# 2_-_PWR.net
KiCad netlist of a schematic drawn in Altium Designer
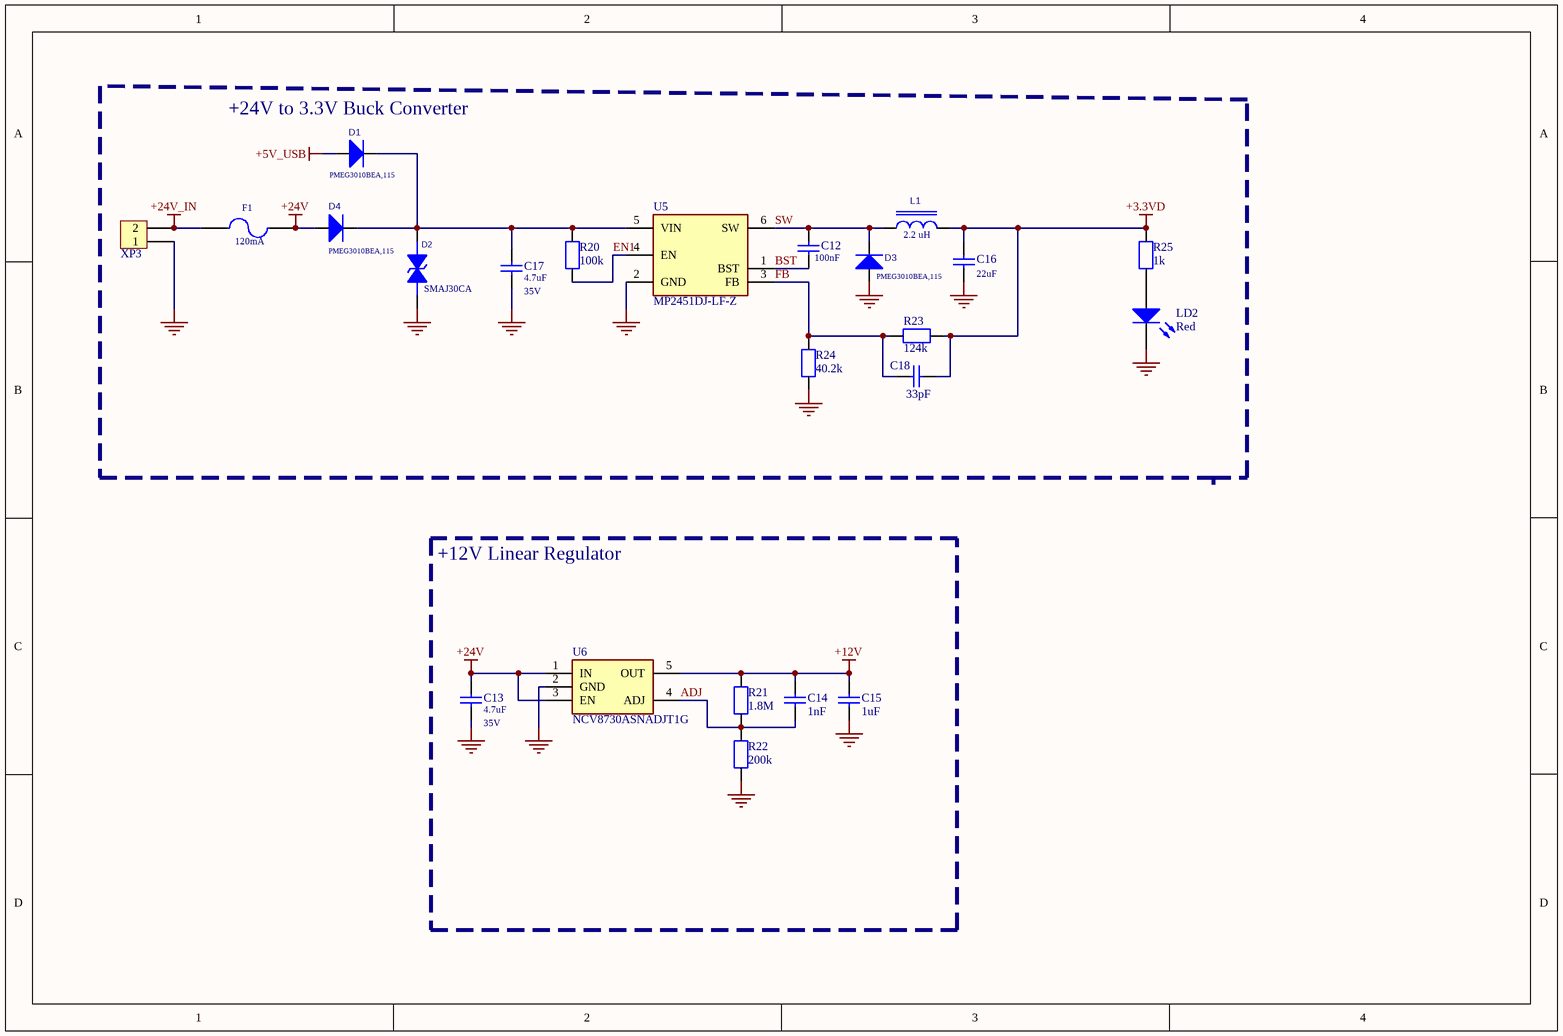
[diagram p0: [2] - PWR.SchDoc]

(export (version "E")
  (design (tool "Eeschema 10.0.6"))
  (components
    (comp (ref "C12")
      (value "100nF")
      (footprint "CC0603")
      (description "SMD Multilayer Ceramic Capacitor, 0.1 µF, 50 V, 0603 [1608 Metric], ± 10%, X7R, MC")
      (fields
        (field (name "MANUFACTURER") "MULTICOMP")
        (field (name "MANUFACTURER PART NUMBER") "MC0603B104K500CT")
      )
      (libsource (lib "YAQF") (part "Capacitors_SMD"))
    )
    (comp (ref "C13")
      (value "4.7uF")
      (footprint "CC0805")
      (description "SMD Multilayer Ceramic Capacitor, 4.7 µF, 35 V, 0805 [2012 Metric], ± 10%, X7R, CGA")
      (fields
        (field (name "MANUFACTURER") "TDK")
        (field (name "MANUFACTURER PART NUMBER") "CGA4J1X7R1V475K125AC")
        (field (name "WORKING VOLTAGE") "35V")
      )
      (libsource (lib "ENEL004.201.001") (part "Capacitors_SMD_10"))
    )
    (comp (ref "C14")
      (value "1nF")
      (footprint "CC0603")
      (description "CERAMIC CAPACITOR 1000PF, 50V, X7R, 20%, 0603")
      (fields
        (field (name "MANUFACTURER") "MULTICOMP")
        (field (name "MANUFACTURER PART NUMBER") "MC0603B102M500CT")
      )
      (libsource (lib "ENEL004.201.001") (part "Capacitors_SMD_6"))
    )
    (comp (ref "C15")
      (value "1uF")
      (footprint "CC0603")
      (description "SMD Multilayer Ceramic Capacitor, 1 µF, 16 V, 0603 [1608 Metric], ± 10%, X7R, MC")
      (fields
        (field (name "MANUFACTURER") "MULTICOMP")
        (field (name "MANUFACTURER PART NUMBER") "MC0603B105K160CT")
      )
      (libsource (lib "YAQF") (part "Capacitors_SMD"))
    )
    (comp (ref "C16")
      (value "22uF")
      (footprint "CC0805")
      (description "SMD Multilayer Ceramic Capacitor, 22 µF, 6.3 V, 0805 [2012 Metric], ± 20%, X5R, GRM Series")
      (fields
        (field (name "MANUFACTURER") "MURATA")
        (field (name "MANUFACTURER PART NUMBER") "GRM21BR60J226ME39K")
      )
      (libsource (lib "ENEL004.201.001") (part "Capacitors_SMD_10"))
    )
    (comp (ref "C17")
      (value "4.7uF")
      (footprint "CC0805")
      (description "SMD Multilayer Ceramic Capacitor, 4.7 µF, 35 V, 0805 [2012 Metric], ± 10%, X7R, CGA")
      (fields
        (field (name "MANUFACTURER") "TDK")
        (field (name "MANUFACTURER PART NUMBER") "CGA4J1X7R1V475K125AC")
        (field (name "WORKING VOLTAGE") "35V")
      )
      (libsource (lib "ENEL004.201.001") (part "Capacitors_SMD_10"))
    )
    (comp (ref "C18")
      (value "33pF")
      (footprint "CC0603")
      (description "SMD Multilayer Ceramic Capacitor, 33 pF, 50 V, 0603 [1608 Metric], ± 5%, C0G / NP0, MC")
      (fields
        (field (name "MANUFACTURER") "MULTICOMP")
        (field (name "MANUFACTURER PART NUMBER") "MC0603N330J500CT")
      )
      (libsource (lib "ENEL004.201.001") (part "Capacitors_SMD_14"))
    )
    (comp (ref "D1")
      (value "Diode")
      (footprint "SOD323")
      (description "Schottky Rectifier, Barrier, 30 V, 1 A, Single, SOD-323, 2 Pins, 560 mV")
      (fields
        (field (name "MANUFACTURER PART NUMBER") "PMEG3010BEA,115")
        (field (name "PART NUMBER") "PMEG3010BEA,115")
        (field (name "VOLTAGE") "30V")
      )
      (libsource (lib "Aldiva_Altium_Library") (part "Diode"))
    )
    (comp (ref "D2")
      (value "SMAJ30CA")
      (footprint "SMA")
      (description "TVS Diode, TRANSZORB SMAJ, Bidirectional, 30 V, 48.4 V, DO-214AC (SMA), 2 Pins")
      (fields (field (name "VOLTAGE") "30V") (field (name "MANUFACTURER") "BOURNS"))
      (libsource (lib "Aldiva_Altium_Library") (part "Zenner_diode_bidir"))
    )
    (comp (ref "D3")
      (value "Diode")
      (footprint "SOD323")
      (description "Schottky Rectifier, Barrier, 30 V, 1 A, Single, SOD-323, 2 Pins, 560 mV")
      (fields
        (field (name "MANUFACTURER PART NUMBER") "PMEG3010BEA,115")
        (field (name "PART NUMBER") "PMEG3010BEA,115")
        (field (name "VOLTAGE") "30V")
      )
      (libsource (lib "Aldiva_Altium_Library") (part "Diode"))
    )
    (comp (ref "D4")
      (value "PMEG3010BEA,115")
      (footprint "SOD323")
      (description "Schottky Rectifier, Barrier, 30 V, 1 A, Single, SOD-323, 2 Pins, 560 mV")
      (fields (field (name "VOLTAGE") "30V") (field (name "MANUFACTURER") "NEXPERIA"))
      (libsource (lib "1-10V_PIR_V1.0") (part "PMEG3010BEA,115"))
    )
    (comp (ref "F1")
      (value "0ZCJ0016FF2E")
      (footprint "FUSE1206")
      (description "RESETTABLE FUSE, PTC, 48VDC, 120mA, SMD, FULL REEL")
      (fields
        (field (name "PART NUMBER") "NANOSMDC012F-2")
        (field (name "CURRENT") "120mA")
        (field (name "VOLTAGE") "48VDC")
      )
      (libsource (lib "Aldiva_Altium_Library") (part "RXEF010"))
    )
    (comp (ref "L1")
      (value "2.2 uH")
      (footprint "1-10V_PIR_V1.0:TYS30102R2N10")
      (description "Power Inductor (SMD), 2.2 µH, 1.09 A, Shielded, 1.15 A, TYS")
      (fields (field (name "PART NUMBER") "TYS30102R2N-10") (field (name "TOLERANCE") "30%"))
      (libsource (lib "Aldiva_Altium_Library") (part "INDUCTOR"))
    )
    (comp (ref "LD2")
      (value "LED")
      (footprint "LED0603")
      (description "LED RED 0603 SMD")
      (fields
        (field (name "PART NUMBER") "TLMS1000-GS08")
        (field (name "COLOR") "Red")
        (field (name "VOLTAGE") "1.8V")
        (field (name "PUBLISHER") "dlegkobyt")
      )
      (libsource (lib "Aldiva_Altium_Library") (part "LED"))
    )
    (comp (ref "R20")
      (value "100k")
      (footprint "RC0603")
      (description "SMD Chip Resistor, 100 kohm, ± 1%, 100 mW, 0603 [1608 Metric], Thick Film, General Purpose")
      (fields
        (field (name "MANUFACTURER") "MULTICOMP")
        (field (name "MANUFACTURER PART NUMBER") "MCWR06X1003FTL")
      )
      (libsource (lib "ENEL004.201.001") (part "Resistors_SMD_4"))
    )
    (comp (ref "R21")
      (value "1.8M")
      (footprint "RC0603")
      (description "SMD Chip Resistor, 1.8 Mohm, ± 1%, 100 mW, 0603 [1608 Metric], Thick Film, General Purpose")
      (fields
        (field (name "MANUFACTURER") "YAGEO")
        (field (name "MANUFACTURER PART NUMBER") "RC0603FR-071M8L")
      )
      (libsource (lib "") (part "Resistors_SMD_4_1"))
    )
    (comp (ref "R22")
      (value "200k")
      (footprint "RC0603")
      (description "SMD Chip Resistor, 200 kohm, ± 1%, 100 mW, 0603 [1608 Metric], Thick Film, General Purpose")
      (fields
        (field (name "MANUFACTURER") "YAGEO")
        (field (name "MANUFACTURER PART NUMBER") "RC0603FR-07200KL")
      )
      (libsource (lib "") (part "Resistors_SMD_4_1"))
    )
    (comp (ref "R23")
      (value "124k")
      (footprint "RC0603")
      (description "SMD Chip Resistor, 124 kohm, ± 1%, 100 mW, 0603 [1608 Metric], Thick Film, General Purpose")
      (fields
        (field (name "MANUFACTURER") "YAGEO")
        (field (name "MANUFACTURER PART NUMBER") "RC0603FR-07124KL")
      )
      (libsource (lib "") (part "Resistors_SMD_4_2"))
    )
    (comp (ref "R24")
      (value "40.2k")
      (footprint "RC0603")
      (description "Thick Film Resistors - SMD 32.4 Ohms 100 mW 0603 1%")
      (fields
        (field (name "MANUFACTURER") "YAGEO")
        (field (name "MANUFACTURER PART NUMBER") "RC0603FR-1340K2L")
      )
      (libsource (lib "ENEL004.201.001") (part "Resistors_SMD_4"))
    )
    (comp (ref "R25")
      (value "1k")
      (footprint "RC0603")
      (description "SMD Chip Resistor, 1 kohm, ± 1%, 100 mW, 0603 [1608 Metric], Thick Film, General Purpose")
      (fields
        (field (name "MANUFACTURER") "MULTICOMP")
        (field (name "MANUFACTURER PART NUMBER") "MCWR06X1001FTL")
      )
      (libsource (lib "ENEL004.201.001") (part "Resistors_SMD"))
    )
    (comp (ref "U5")
      (value "MP2451DJ-LF-Z")
      (footprint "SOT95P280X110-6N")
      (fields (field (name "MANUFACTURER") "MPS"))
      (libsource (lib "1-10V_PIR_V1.0_1") (part "MP2451DJ-LF-Z"))
    )
    (comp (ref "U6")
      (value "NCV8730ASNADJT1G")
      (footprint "SamacSys:SOT95P275X110-5N")
      (description "LDO, ADJ, 0.15A, Input Voltage Max 38V, -40 TO 125DEG C")
      (fields
        (field (name "MANUFACTURER") "Onsemi")
        (field (name "MOUSER PART NUMBER") "863-NCV8730ASNADJT1G")
      )
      (libsource (lib "SamacSys") (part "NCV8730ASNADJT1G"))
    )
    (comp (ref "XP3")
      (value "Header 2x1pins")
      (footprint "MC 1,5_2-G-3,81")
      (description "Terminal Block, Header, 3.81 mm, 2 Ways, 8 A, 160 V, Through Hole Right Angle")
      (fields
        (field (name "PART NUMBER") "MC 1,5/ 2-G-3,81")
        (field (name "MANUFACTURER") "PHOENIX CONTACT")
        (field (name "PUBLISHER") "dlegkobyt")
      )
      (libsource (lib "Aldiva_Altium_Library") (part "Header 2x1pins"))
    )
  )
  (nets
    (net (code "1") (name "+3.3VD") (class "Default")
      (node (ref "C16") (pin "1") (pinfunction "1_1") (pintype "passive"))
      (node (ref "C18") (pin "2") (pinfunction "2_2") (pintype "passive"))
      (node (ref "L1") (pin "2") (pinfunction "2_2") (pintype "passive"))
      (node (ref "R23") (pin "2") (pinfunction "2_2") (pintype "passive"))
      (node (ref "R25") (pin "2") (pinfunction "2_2") (pintype "passive"))
    )
    (net (code "2") (name "+5V_USB") (class "Default")
      (node (ref "D1") (pin "2") (pinfunction "A_2") (pintype "passive"))
    )
    (net (code "3") (name "+12V") (class "Default")
      (node (ref "C14") (pin "1") (pinfunction "1_1") (pintype "passive"))
      (node (ref "C15") (pin "1") (pinfunction "1_1") (pintype "passive"))
      (node (ref "R21") (pin "2") (pinfunction "2_2") (pintype "passive"))
      (node (ref "U6") (pin "5") (pinfunction "OUT_5") (pintype "passive"))
    )
    (net (code "4") (name "+24V") (class "Default")
      (node (ref "C13") (pin "1") (pinfunction "1_1") (pintype "passive"))
      (node (ref "D4") (pin "2") (pinfunction "A_2") (pintype "passive"))
      (node (ref "F1") (pin "2") (pinfunction "2_2") (pintype "passive"))
      (node (ref "U6") (pin "1") (pinfunction "IN_1") (pintype "passive"))
      (node (ref "U6") (pin "3") (pinfunction "EN_3") (pintype "passive"))
    )
    (net (code "5") (name "+24V_IN") (class "Default")
      (node (ref "F1") (pin "1") (pinfunction "1_1") (pintype "passive"))
      (node (ref "XP3") (pin "2") (pinfunction "2_2") (pintype "passive"))
    )
    (net (code "6") (name "/ADJ") (class "Default")
      (node (ref "C14") (pin "2") (pinfunction "2_2") (pintype "passive"))
      (node (ref "R21") (pin "1") (pinfunction "1_1") (pintype "passive"))
      (node (ref "R22") (pin "2") (pinfunction "2_2") (pintype "passive"))
      (node (ref "U6") (pin "4") (pinfunction "ADJ_4") (pintype "passive"))
    )
    (net (code "7") (name "/BST") (class "Default")
      (node (ref "C12") (pin "2") (pinfunction "2_2") (pintype "passive"))
      (node (ref "U5") (pin "1") (pinfunction "BST_1") (pintype "passive"))
    )
    (net (code "8") (name "/EN1") (class "Default")
      (node (ref "R20") (pin "2") (pinfunction "2_2") (pintype "passive"))
      (node (ref "U5") (pin "4") (pinfunction "EN_4") (pintype "passive"))
    )
    (net (code "9") (name "/FB") (class "Default")
      (node (ref "C18") (pin "1") (pinfunction "1_1") (pintype "passive"))
      (node (ref "R23") (pin "1") (pinfunction "1_1") (pintype "passive"))
      (node (ref "R24") (pin "1") (pinfunction "1_1") (pintype "passive"))
      (node (ref "U5") (pin "3") (pinfunction "FB_3") (pintype "passive"))
    )
    (net (code "10") (name "/SW") (class "Default")
      (node (ref "C12") (pin "1") (pinfunction "1_1") (pintype "passive"))
      (node (ref "D3") (pin "1") (pinfunction "K_1") (pintype "passive"))
      (node (ref "L1") (pin "1") (pinfunction "1_1") (pintype "passive"))
      (node (ref "U5") (pin "6") (pinfunction "SW_6") (pintype "passive"))
    )
    (net (code "11") (name "GND") (class "Default")
      (node (ref "C13") (pin "2") (pinfunction "2_2") (pintype "passive"))
      (node (ref "C15") (pin "2") (pinfunction "2_2") (pintype "passive"))
      (node (ref "C16") (pin "2") (pinfunction "2_2") (pintype "passive"))
      (node (ref "C17") (pin "2") (pinfunction "2_2") (pintype "passive"))
      (node (ref "D2") (pin "1") (pinfunction "1_1") (pintype "passive"))
      (node (ref "D3") (pin "2") (pinfunction "A_2") (pintype "passive"))
      (node (ref "LD2") (pin "1") (pinfunction "K_1") (pintype "passive"))
      (node (ref "R22") (pin "1") (pinfunction "1_1") (pintype "passive"))
      (node (ref "R24") (pin "2") (pinfunction "2_2") (pintype "passive"))
      (node (ref "U5") (pin "2") (pinfunction "GND_2") (pintype "power_in"))
      (node (ref "U6") (pin "2") (pinfunction "GND_2") (pintype "passive"))
      (node (ref "XP3") (pin "1") (pinfunction "1_1") (pintype "passive"))
    )
    (net (code "12") (name "Net-(D1-K)") (class "Default")
      (node (ref "C17") (pin "1") (pinfunction "1_1") (pintype "passive"))
      (node (ref "D1") (pin "1") (pinfunction "K_1") (pintype "passive"))
      (node (ref "D2") (pin "2") (pinfunction "2_2") (pintype "passive"))
      (node (ref "D4") (pin "1") (pinfunction "K_1") (pintype "passive"))
      (node (ref "R20") (pin "1") (pinfunction "1_1") (pintype "passive"))
      (node (ref "U5") (pin "5") (pinfunction "VIN_5") (pintype "power_in"))
    )
    (net (code "13") (name "Net-(LD2-A)") (class "Default")
      (node (ref "LD2") (pin "2") (pinfunction "A_2") (pintype "passive"))
      (node (ref "R25") (pin "1") (pinfunction "1_1") (pintype "passive"))
    )
  )
)
